# OLED_Adapter_Alle_Bauteile.net
KiCad netlist of a schematic drawn in EAGLE
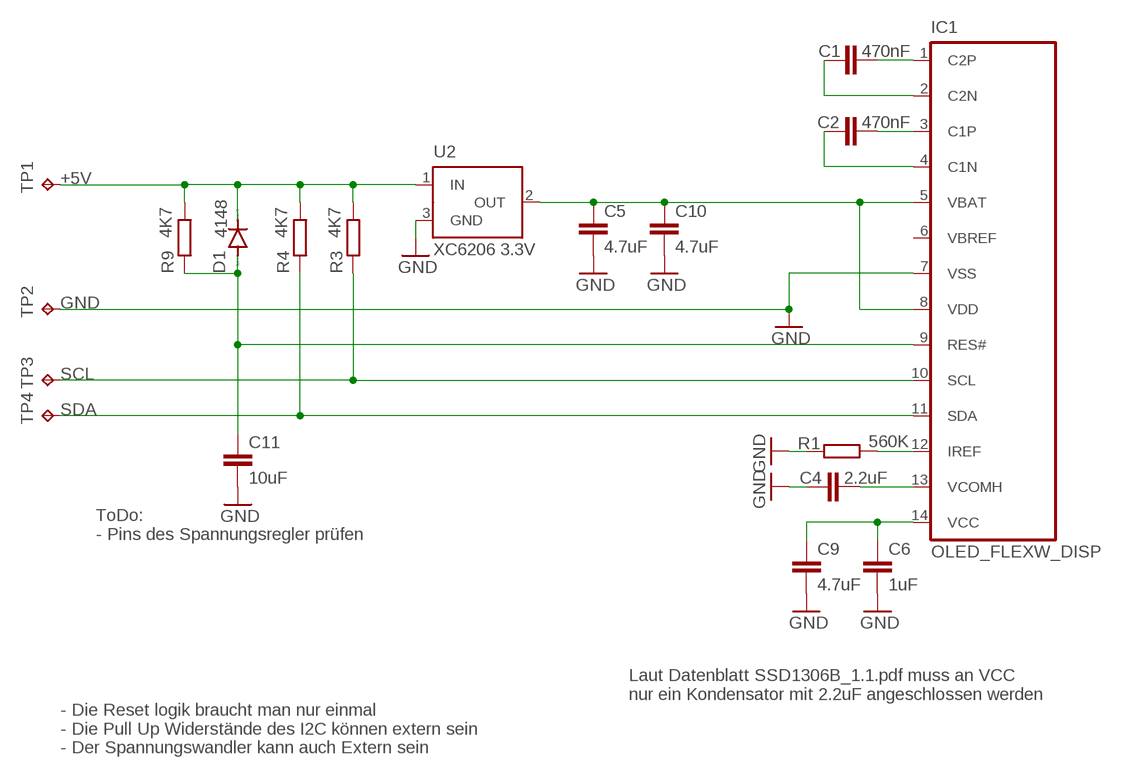
[diagram p0: schematic, sheet 1]

(export (version "E")
  (design (tool "Eeschema 10.0.6"))
  (components
    (comp (ref "C1")
      (value "470nF")
      (footprint "eagle-import:C0603")
      (libsource (lib "eagle-import") (part "C-EUC0603"))
    )
    (comp (ref "C2")
      (value "470nF")
      (footprint "eagle-import:C0603")
      (libsource (lib "eagle-import") (part "C-EUC0603"))
    )
    (comp (ref "C4")
      (value "2.2uF")
      (footprint "eagle-import:C0603")
      (libsource (lib "eagle-import") (part "C-EUC0603"))
    )
    (comp (ref "C5")
      (value "4.7uF")
      (footprint "eagle-import:C0603")
      (libsource (lib "eagle-import") (part "C-EUC0603"))
    )
    (comp (ref "C6")
      (value "1uF")
      (footprint "eagle-import:C0603")
      (libsource (lib "eagle-import") (part "C-EUC0603"))
    )
    (comp (ref "C9")
      (value "4.7uF")
      (footprint "eagle-import:C0603")
      (libsource (lib "eagle-import") (part "C-EUC0603"))
    )
    (comp (ref "C10")
      (value "4.7uF")
      (footprint "eagle-import:C0603")
      (libsource (lib "eagle-import") (part "C-EUC0603"))
    )
    (comp (ref "C11")
      (value "10uF")
      (footprint "eagle-import:C0603")
      (libsource (lib "eagle-import") (part "C-EUC0603"))
    )
    (comp (ref "D1")
      (value "4148")
      (footprint "eagle-import:SOD-123_MINI-SMA")
      (libsource (lib "eagle-import") (part "CGRM400-G1"))
    )
    (comp (ref "IC1")
      (value "OLED_FLEXW_DISP")
      (footprint "eagle-import:OLED_FLEX_W_DISP")
      (libsource (lib "eagle-import") (part "OLED_FLEXW_DISP"))
    )
    (comp (ref "R1")
      (value "560K")
      (footprint "eagle-import:R0603")
      (libsource (lib "eagle-import") (part "R-EU_R0603"))
    )
    (comp (ref "R3")
      (value "4K7")
      (footprint "eagle-import:R0603")
      (libsource (lib "eagle-import") (part "R-EU_R0603"))
    )
    (comp (ref "R4")
      (value "4K7")
      (footprint "eagle-import:R0603")
      (libsource (lib "eagle-import") (part "R-EU_R0603"))
    )
    (comp (ref "R9")
      (value "4K7")
      (footprint "eagle-import:R0603")
      (libsource (lib "eagle-import") (part "R-EU_R0603"))
    )
    (comp (ref "TP1")
      (value "TPTP10SQ")
      (footprint "eagle-import:TP10SQ")
      (libsource (lib "eagle-import") (part "TPTP10SQ"))
    )
    (comp (ref "TP2")
      (value "TPTP10R")
      (footprint "eagle-import:TP10R")
      (libsource (lib "eagle-import") (part "TPTP10R"))
    )
    (comp (ref "TP3")
      (value "TPTP10R")
      (footprint "eagle-import:TP10R")
      (libsource (lib "eagle-import") (part "TPTP10R"))
    )
    (comp (ref "TP4")
      (value "TPTP10R")
      (footprint "eagle-import:TP10R")
      (libsource (lib "eagle-import") (part "TPTP10R"))
    )
    (comp (ref "U2")
      (value "XC6206 3.3V")
      (footprint "eagle-import:SOT23")
      (fields (field (name "MF") "MAXIM") (field (name "MPN") "MAX6520EUR-T"))
      (libsource (lib "eagle-import") (part "MAX6520"))
    )
  )
  (nets
    (net (code "1") (name "/+5V") (class "Default")
      (node (ref "D1") (pin "C") (pinfunction "C_C") (pintype "passive"))
      (node (ref "R3") (pin "2") (pinfunction "2_2") (pintype "passive"))
      (node (ref "R4") (pin "2") (pinfunction "2_2") (pintype "passive"))
      (node (ref "R9") (pin "2") (pinfunction "2_2") (pintype "passive"))
      (node (ref "TP1") (pin "TP") (pinfunction "TP_TP") (pintype "input"))
      (node (ref "U2") (pin "1") (pinfunction "IN_1") (pintype "input"))
    )
    (net (code "2") (name "/SCL") (class "Default")
      (node (ref "IC1") (pin "10") (pinfunction "SCL_10") (pintype "bidirectional"))
      (node (ref "R3") (pin "1") (pinfunction "1_1") (pintype "passive"))
      (node (ref "TP3") (pin "TP") (pinfunction "TP_TP") (pintype "input"))
    )
    (net (code "3") (name "/SDA") (class "Default")
      (node (ref "IC1") (pin "11") (pinfunction "SDA_11") (pintype "bidirectional"))
      (node (ref "R4") (pin "1") (pinfunction "1_1") (pintype "passive"))
      (node (ref "TP4") (pin "TP") (pinfunction "TP_TP") (pintype "input"))
    )
    (net (code "4") (name "GND") (class "Default")
      (node (ref "C10") (pin "2") (pinfunction "2_2") (pintype "passive"))
      (node (ref "C11") (pin "2") (pinfunction "2_2") (pintype "passive"))
      (node (ref "C4") (pin "1") (pinfunction "1_1") (pintype "passive"))
      (node (ref "C5") (pin "2") (pinfunction "2_2") (pintype "passive"))
      (node (ref "C6") (pin "2") (pinfunction "2_2") (pintype "passive"))
      (node (ref "C9") (pin "2") (pinfunction "2_2") (pintype "passive"))
      (node (ref "IC1") (pin "7") (pinfunction "VSS_7") (pintype "power_in"))
      (node (ref "R1") (pin "1") (pinfunction "1_1") (pintype "passive"))
      (node (ref "TP2") (pin "TP") (pinfunction "TP_TP") (pintype "input"))
      (node (ref "U2") (pin "3") (pinfunction "GND_3") (pintype "power_in"))
    )
    (net (code "5") (name "Net-(IC1-C1N)") (class "Default")
      (node (ref "C2") (pin "1") (pinfunction "1_1") (pintype "passive"))
      (node (ref "IC1") (pin "4") (pinfunction "C1N_4") (pintype "bidirectional"))
    )
    (net (code "6") (name "Net-(IC1-C1P)") (class "Default")
      (node (ref "C2") (pin "2") (pinfunction "2_2") (pintype "passive"))
      (node (ref "IC1") (pin "3") (pinfunction "C1P_3") (pintype "bidirectional"))
    )
    (net (code "7") (name "Net-(IC1-C2N)") (class "Default")
      (node (ref "C1") (pin "1") (pinfunction "1_1") (pintype "passive"))
      (node (ref "IC1") (pin "2") (pinfunction "C2N_2") (pintype "bidirectional"))
    )
    (net (code "8") (name "Net-(IC1-C2P)") (class "Default")
      (node (ref "C1") (pin "2") (pinfunction "2_2") (pintype "passive"))
      (node (ref "IC1") (pin "1") (pinfunction "C2P_1") (pintype "bidirectional"))
    )
    (net (code "9") (name "Net-(IC1-IREF)") (class "Default")
      (node (ref "IC1") (pin "12") (pinfunction "IREF_12") (pintype "input"))
      (node (ref "R1") (pin "2") (pinfunction "2_2") (pintype "passive"))
    )
    (net (code "10") (name "Net-(IC1-RES#)") (class "Default")
      (node (ref "C11") (pin "1") (pinfunction "1_1") (pintype "passive"))
      (node (ref "D1") (pin "A") (pinfunction "A_A") (pintype "passive"))
      (node (ref "IC1") (pin "9") (pinfunction "RES#_9") (pintype "input"))
      (node (ref "R9") (pin "1") (pinfunction "1_1") (pintype "passive"))
    )
    (net (code "11") (name "Net-(IC1-VBAT)") (class "Default")
      (node (ref "C10") (pin "1") (pinfunction "1_1") (pintype "passive"))
      (node (ref "C5") (pin "1") (pinfunction "1_1") (pintype "passive"))
      (node (ref "IC1") (pin "5") (pinfunction "VBAT_5") (pintype "power_in"))
      (node (ref "IC1") (pin "8") (pinfunction "VDD_8") (pintype "power_in"))
      (node (ref "U2") (pin "2") (pinfunction "OUT_2") (pintype "output"))
    )
    (net (code "12") (name "Net-(IC1-VCC)") (class "Default")
      (node (ref "C6") (pin "1") (pinfunction "1_1") (pintype "passive"))
      (node (ref "C9") (pin "1") (pinfunction "1_1") (pintype "passive"))
      (node (ref "IC1") (pin "14") (pinfunction "VCC_14") (pintype "power_in"))
    )
    (net (code "13") (name "Net-(IC1-VCOMH)") (class "Default")
      (node (ref "C4") (pin "2") (pinfunction "2_2") (pintype "passive"))
      (node (ref "IC1") (pin "13") (pinfunction "VCOMH_13") (pintype "input"))
    )
    (net (code "14") (name "unconnected-(IC1-VBREF-Pad6)") (class "Default")
      (node (ref "IC1") (pin "6") (pinfunction "VBREF_6") (pintype "input"))
    )
  )
)
